# Headers_v0.net
KiCad netlist of a schematic drawn in Altium Designer
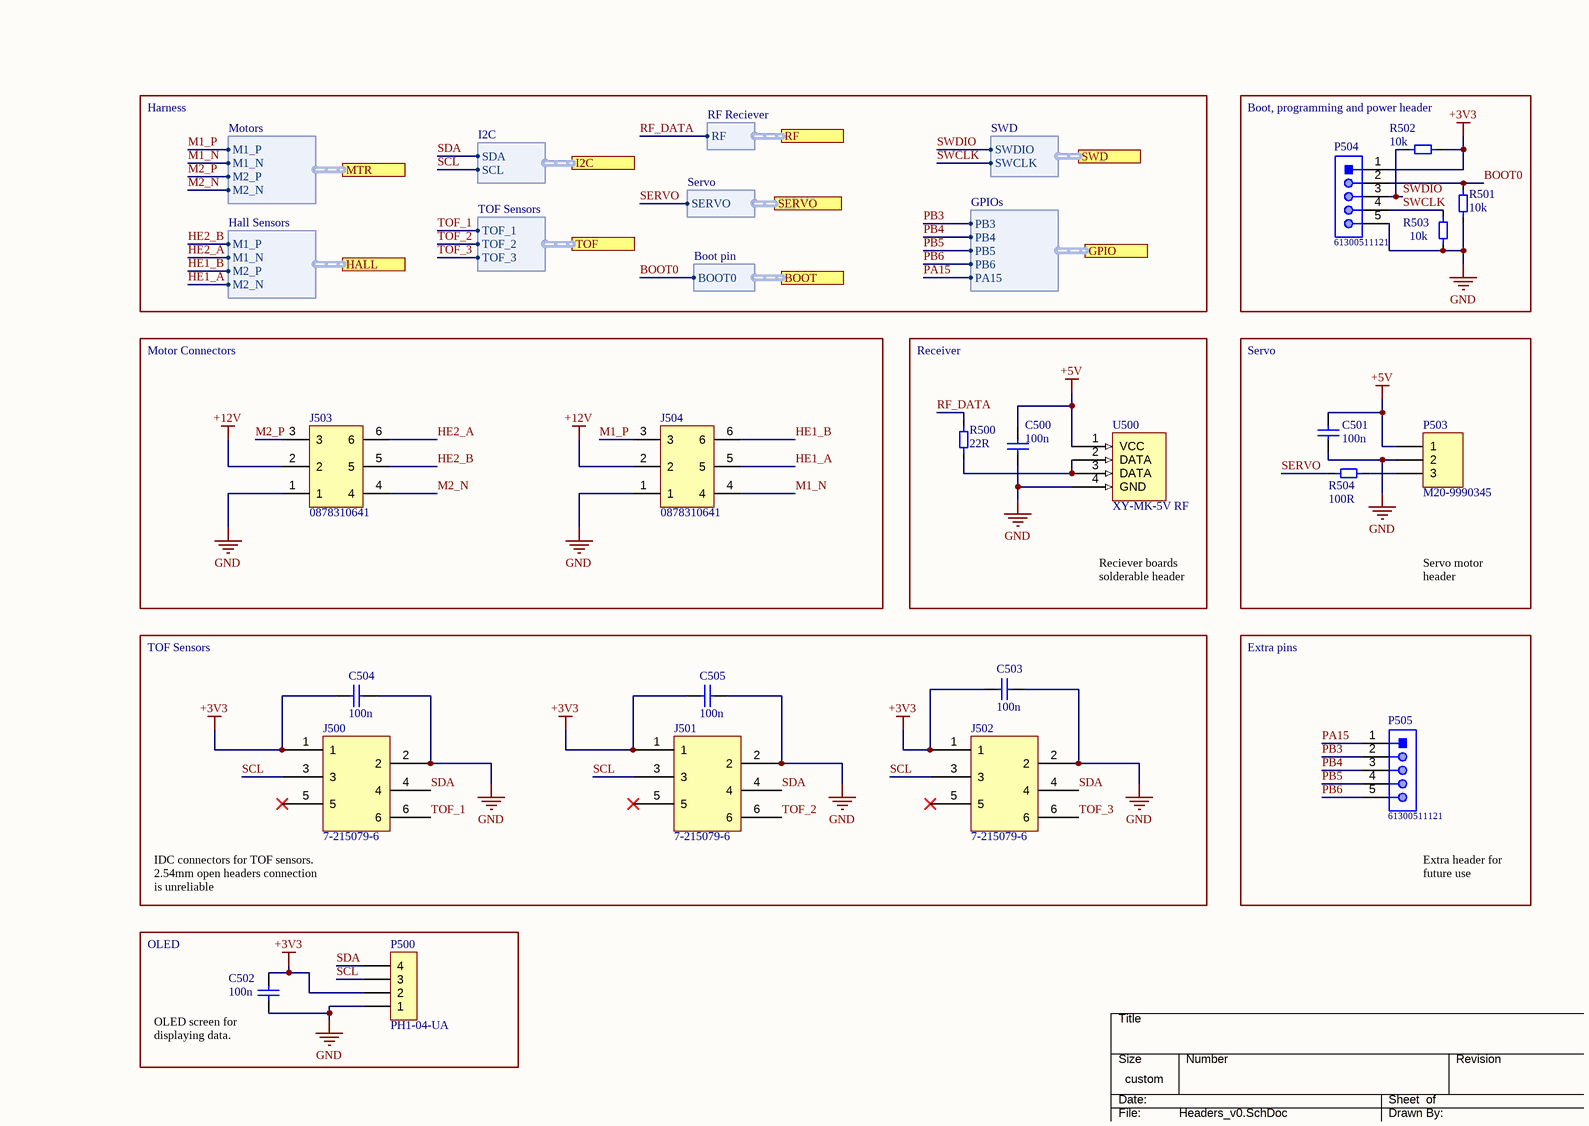
[diagram p0: Headers_v0.SchDoc]

(export (version "E")
  (design (tool "Eeschema 10.0.6"))
  (components
    (comp (ref "C500")
      (value "100n")
      (footprint "MLCC_0603_M")
      (description "MLCC, 0603, 100n, 10%, 50V, X7R")
      (fields (field (name "VOLTAGE") "50V") (field (name "TOLERANCE") "10%"))
      (libsource (lib "Krakul Vault") (part "CAPACITOR_NONPOL_IEC"))
    )
    (comp (ref "C501")
      (value "100n")
      (footprint "MLCC_0603_M")
      (description "MLCC, 0603, 100n, 10%, 50V, X7R")
      (fields (field (name "VOLTAGE") "50V") (field (name "TOLERANCE") "10%"))
      (libsource (lib "Krakul Vault") (part "CAPACITOR_NONPOL_IEC"))
    )
    (comp (ref "C502")
      (value "100n")
      (footprint "MLCC_0603_M")
      (description "MLCC, 0603, 100n, 10%, 50V, X7R")
      (fields (field (name "VOLTAGE") "50V") (field (name "TOLERANCE") "10%"))
      (libsource (lib "Krakul Vault") (part "CAPACITOR_NONPOL_IEC"))
    )
    (comp (ref "C503")
      (value "100n")
      (footprint "MLCC_0603_M")
      (description "MLCC, 0603, 100n, 10%, 50V, X7R")
      (fields (field (name "VOLTAGE") "50V") (field (name "TOLERANCE") "10%"))
      (libsource (lib "Krakul Vault") (part "CAPACITOR_NONPOL_IEC"))
    )
    (comp (ref "C504")
      (value "100n")
      (footprint "MLCC_0603_M")
      (description "MLCC, 0603, 100n, 10%, 50V, X7R")
      (fields (field (name "VOLTAGE") "50V") (field (name "TOLERANCE") "10%"))
      (libsource (lib "Krakul Vault") (part "CAPACITOR_NONPOL_IEC"))
    )
    (comp (ref "C505")
      (value "100n")
      (footprint "MLCC_0603_M")
      (description "MLCC, 0603, 100n, 10%, 50V, X7R")
      (fields (field (name "VOLTAGE") "50V") (field (name "TOLERANCE") "10%"))
      (libsource (lib "Krakul Vault") (part "CAPACITOR_NONPOL_IEC"))
    )
    (comp (ref "J500")
      (value "7-215079-6")
      (footprint "7-215079-6-Footprint-1")
      (description "Conn FFC Connector F 6 POS 1.27mm Solder ST Thru-Hole Automotive Box/Carton")
      (fields (field (name "MANUFACTURER") "TE Connectivity"))
      (libsource (lib "Krakul Vault") (part "7-215079-6"))
    )
    (comp (ref "J501")
      (value "7-215079-6")
      (footprint "7-215079-6-Footprint-1")
      (description "Conn FFC Connector F 6 POS 1.27mm Solder ST Thru-Hole Automotive Box/Carton")
      (fields (field (name "MANUFACTURER") "TE Connectivity"))
      (libsource (lib "Krakul Vault") (part "7-215079-6"))
    )
    (comp (ref "J502")
      (value "7-215079-6")
      (footprint "7-215079-6-Footprint-1")
      (description "Conn FFC Connector F 6 POS 1.27mm Solder ST Thru-Hole Automotive Box/Carton")
      (fields (field (name "MANUFACTURER") "TE Connectivity"))
      (libsource (lib "Krakul Vault") (part "7-215079-6"))
    )
    (comp (ref "J503")
      (value "0878310641")
      (footprint "0878310641")
      (description "Conn Shrouded Header (2 Sides) HDR 6 POS 2mm Solder ST Top Entry Thru-Hole Milli-Grid Tube")
      (fields (field (name "MANUFACTURER") "Molex"))
      (libsource (lib "Krakul Vault") (part "0878310641"))
    )
    (comp (ref "J504")
      (value "0878310641")
      (footprint "0878310641")
      (description "Conn Shrouded Header (2 Sides) HDR 6 POS 2mm Solder ST Top Entry Thru-Hole Milli-Grid Tube")
      (fields (field (name "MANUFACTURER") "Molex"))
      (libsource (lib "Krakul Vault") (part "0878310641"))
    )
    (comp (ref "P500")
      (value "PH1-04-UA")
      (footprint "4Pos Pin Header Vertical")
      (description "4 POS 2.54mm Vertical THT Header")
      (fields (field (name "MANUFACTURER") "Adam Tech"))
      (libsource (lib "Krakul Vault") (part "4POS GENERIC"))
    )
    (comp (ref "P503")
      (value "M20-9990345")
      (footprint "3Pos Pin Header")
      (description "Connector Header Through Hole 3 position 0.100\" (2.54mm)")
      (fields (field (name "MANUFACTURER") "Harwin Inc."))
      (libsource (lib "Krakul Vault") (part "3 pin header"))
    )
    (comp (ref "P504")
      (value "61300511121")
      (footprint "61300511121")
      (description "Conn Unshrouded Header HDR 5 POS 2.54mm Solder ST Top Entry Thru-Hole Bag")
      (fields (field (name "MANUFACTURER") "Wurth"))
      (libsource (lib "Krakul Vault") (part "WE-CN-1P-M-R5"))
    )
    (comp (ref "P505")
      (value "61300511121")
      (footprint "61300511121")
      (description "Conn Unshrouded Header HDR 5 POS 2.54mm Solder ST Top Entry Thru-Hole Bag")
      (fields (field (name "MANUFACTURER") "Wurth"))
      (libsource (lib "") (part "WE-CN-1P-M-R5_1"))
    )
    (comp (ref "R500")
      (value "22R")
      (footprint "Resistor_0603_M")
      (description "Resistor, 0603, 22R, 1%, 1/10W")
      (fields (field (name "TOLERANCE") "1%") (field (name "MANUFACTURER") "Any"))
      (libsource (lib "Krakul Vault") (part "RESISTOR_GENERIC_IEC"))
    )
    (comp (ref "R501")
      (value "10k")
      (footprint "Resistor_0603_M")
      (description "Resistor, 0603, 10k, ≤5%, ≥1/16W")
      (fields (field (name "MANUFACTURER") "Any"))
      (libsource (lib "Krakul Vault") (part "RESISTOR_GENERIC_IEC"))
    )
    (comp (ref "R502")
      (value "10k")
      (footprint "Resistor_0603_M")
      (description "Resistor, 0603, 10k, 1%, 1/10W")
      (fields (field (name "MANUFACTURER") "Any") (field (name "TOLERANCE") "1%"))
      (libsource (lib "Krakul Vault") (part "RESISTOR_GENERIC_IEC"))
    )
    (comp (ref "R503")
      (value "10k")
      (footprint "Resistor_0603_M")
      (description "Resistor, 0603, 10k, 1%, 1/10W")
      (fields (field (name "MANUFACTURER") "Any") (field (name "TOLERANCE") "1%"))
      (libsource (lib "Krakul Vault") (part "RESISTOR_GENERIC_IEC"))
    )
    (comp (ref "R504")
      (value "100R")
      (footprint "Resistor_0603_M")
      (description "Resistor, 0603, 100R, 1%, 1/10W")
      (fields (field (name "POWER") "100mW") (field (name "MANUFACTURER") "Any"))
      (libsource (lib "Krakul Vault") (part "RESISTOR_GENERIC_IEC"))
    )
    (comp (ref "U500")
      (value "XY-MK-5V RF")
      (footprint "2.54mm 4 POS XY-MK-5V RF")
      (description "433MHz reciever module, 5V tolerant")
      (fields (field (name "MANUFACTURER") "Unknown"))
      (libsource (lib "Krakul Vault") (part "XY-MK-5V RF-Symbol-1"))
    )
  )
  (nets
    (net (code "13") (name "+3V3") (class "Default")
      (node (ref "C502") (pin "1") (pinfunction "1_1") (pintype "passive"))
      (node (ref "C503") (pin "1") (pinfunction "1_1") (pintype "passive"))
      (node (ref "C504") (pin "1") (pinfunction "1_1") (pintype "passive"))
      (node (ref "C505") (pin "1") (pinfunction "1_1") (pintype "passive"))
      (node (ref "J500") (pin "1") (pinfunction "1_1") (pintype "passive"))
      (node (ref "J501") (pin "1") (pinfunction "1_1") (pintype "passive"))
      (node (ref "J502") (pin "1") (pinfunction "1_1") (pintype "passive"))
      (node (ref "P500") (pin "2") (pinfunction "2_2") (pintype "passive"))
      (node (ref "P504") (pin "1") (pinfunction "1_1") (pintype "passive"))
      (node (ref "R502") (pin "1") (pinfunction "1_1") (pintype "passive"))
    )
    (net (code "14") (name "+5V") (class "Default")
      (node (ref "C500") (pin "1") (pinfunction "1_1") (pintype "passive"))
      (node (ref "C501") (pin "1") (pinfunction "1_1") (pintype "passive"))
      (node (ref "P503") (pin "1") (pinfunction "1_1") (pintype "passive"))
      (node (ref "U500") (pin "1") (pinfunction "VCC_1") (pintype "input"))
    )
    (net (code "15") (name "+12V") (class "Default")
      (node (ref "J503") (pin "2") (pinfunction "2_2") (pintype "passive"))
      (node (ref "J504") (pin "2") (pinfunction "2_2") (pintype "passive"))
    )
    (net (code "16") (name "/BOOT0") (class "Default")
      (node (ref "P504") (pin "2") (pinfunction "2_2") (pintype "passive"))
      (node (ref "R501") (pin "2") (pinfunction "2_2") (pintype "passive"))
    )
    (net (code "17") (name "/HE1_A") (class "Default")
      (node (ref "J504") (pin "5") (pinfunction "5_5") (pintype "passive"))
    )
    (net (code "18") (name "/HE1_B") (class "Default")
      (node (ref "J504") (pin "6") (pinfunction "6_6") (pintype "passive"))
    )
    (net (code "19") (name "/HE2_A") (class "Default")
      (node (ref "J503") (pin "6") (pinfunction "6_6") (pintype "passive"))
    )
    (net (code "20") (name "/HE2_B") (class "Default")
      (node (ref "J503") (pin "5") (pinfunction "5_5") (pintype "passive"))
    )
    (net (code "21") (name "/M1_N") (class "Default")
      (node (ref "J504") (pin "4") (pinfunction "4_4") (pintype "passive"))
    )
    (net (code "22") (name "/M1_P") (class "Default")
      (node (ref "J504") (pin "3") (pinfunction "3_3") (pintype "passive"))
    )
    (net (code "23") (name "/M2_N") (class "Default")
      (node (ref "J503") (pin "4") (pinfunction "4_4") (pintype "passive"))
    )
    (net (code "24") (name "/M2_P") (class "Default")
      (node (ref "J503") (pin "3") (pinfunction "3_3") (pintype "passive"))
    )
    (net (code "25") (name "/PA15") (class "Default")
      (node (ref "P505") (pin "1") (pinfunction "1_1") (pintype "passive"))
    )
    (net (code "26") (name "/PB3") (class "Default")
      (node (ref "P505") (pin "2") (pinfunction "2_2") (pintype "passive"))
    )
    (net (code "27") (name "/PB4") (class "Default")
      (node (ref "P505") (pin "3") (pinfunction "3_3") (pintype "passive"))
    )
    (net (code "28") (name "/PB5") (class "Default")
      (node (ref "P505") (pin "4") (pinfunction "4_4") (pintype "passive"))
    )
    (net (code "29") (name "/PB6") (class "Default")
      (node (ref "P505") (pin "5") (pinfunction "5_5") (pintype "passive"))
    )
    (net (code "30") (name "/RF_DATA") (class "Default")
      (node (ref "R500") (pin "1") (pinfunction "1_1") (pintype "passive"))
    )
    (net (code "31") (name "/SCL") (class "Default")
      (node (ref "J500") (pin "3") (pinfunction "3_3") (pintype "passive"))
      (node (ref "J501") (pin "3") (pinfunction "3_3") (pintype "passive"))
      (node (ref "J502") (pin "3") (pinfunction "3_3") (pintype "passive"))
      (node (ref "P500") (pin "3") (pinfunction "3_3") (pintype "passive"))
    )
    (net (code "32") (name "/SDA") (class "Default")
      (node (ref "J500") (pin "4") (pinfunction "4_4") (pintype "passive"))
      (node (ref "J501") (pin "4") (pinfunction "4_4") (pintype "passive"))
      (node (ref "J502") (pin "4") (pinfunction "4_4") (pintype "passive"))
      (node (ref "P500") (pin "4") (pinfunction "4_4") (pintype "passive"))
    )
    (net (code "33") (name "/SERVO") (class "Default")
      (node (ref "R504") (pin "2") (pinfunction "2_2") (pintype "passive"))
    )
    (net (code "34") (name "/SWCLK") (class "Default")
      (node (ref "P504") (pin "4") (pinfunction "4_4") (pintype "passive"))
      (node (ref "R503") (pin "2") (pinfunction "2_2") (pintype "passive"))
    )
    (net (code "35") (name "/SWDIO") (class "Default")
      (node (ref "P504") (pin "3") (pinfunction "3_3") (pintype "passive"))
      (node (ref "R502") (pin "2") (pinfunction "2_2") (pintype "passive"))
    )
    (net (code "36") (name "/TOF_1") (class "Default")
      (node (ref "J500") (pin "6") (pinfunction "6_6") (pintype "passive"))
    )
    (net (code "37") (name "/TOF_2") (class "Default")
      (node (ref "J501") (pin "6") (pinfunction "6_6") (pintype "passive"))
    )
    (net (code "38") (name "/TOF_3") (class "Default")
      (node (ref "J502") (pin "6") (pinfunction "6_6") (pintype "passive"))
    )
    (net (code "48") (name "GND") (class "Default")
      (node (ref "C500") (pin "2") (pinfunction "2_2") (pintype "passive"))
      (node (ref "C501") (pin "2") (pinfunction "2_2") (pintype "passive"))
      (node (ref "C502") (pin "2") (pinfunction "2_2") (pintype "passive"))
      (node (ref "C503") (pin "2") (pinfunction "2_2") (pintype "passive"))
      (node (ref "C504") (pin "2") (pinfunction "2_2") (pintype "passive"))
      (node (ref "C505") (pin "2") (pinfunction "2_2") (pintype "passive"))
      (node (ref "J500") (pin "2") (pinfunction "2_2") (pintype "passive"))
      (node (ref "J501") (pin "2") (pinfunction "2_2") (pintype "passive"))
      (node (ref "J502") (pin "2") (pinfunction "2_2") (pintype "passive"))
      (node (ref "J503") (pin "1") (pinfunction "1_1") (pintype "passive"))
      (node (ref "J504") (pin "1") (pinfunction "1_1") (pintype "passive"))
      (node (ref "P500") (pin "1") (pinfunction "1_1") (pintype "passive"))
      (node (ref "P503") (pin "2") (pinfunction "2_2") (pintype "passive"))
      (node (ref "P504") (pin "5") (pinfunction "5_5") (pintype "passive"))
      (node (ref "R501") (pin "1") (pinfunction "1_1") (pintype "passive"))
      (node (ref "R503") (pin "1") (pinfunction "1_1") (pintype "passive"))
      (node (ref "U500") (pin "4") (pinfunction "GND_4") (pintype "input"))
    )
    (net (code "49") (name "Net-(P503-Pad3)") (class "Default")
      (node (ref "P503") (pin "3") (pinfunction "3_3") (pintype "passive"))
      (node (ref "R504") (pin "1") (pinfunction "1_1") (pintype "passive"))
    )
    (net (code "50") (name "Net-(R500-Pad2)") (class "Default")
      (node (ref "R500") (pin "2") (pinfunction "2_2") (pintype "passive"))
      (node (ref "U500") (pin "2") (pinfunction "DATA_2") (pintype "input"))
      (node (ref "U500") (pin "3") (pinfunction "DATA_3") (pintype "input"))
    )
    (net (code "51") (name "unconnected-(J500-Pad5)") (class "Default")
      (node (ref "J500") (pin "5") (pinfunction "5_5") (pintype "passive+no_connect"))
    )
    (net (code "52") (name "unconnected-(J501-Pad5)") (class "Default")
      (node (ref "J501") (pin "5") (pinfunction "5_5") (pintype "passive+no_connect"))
    )
    (net (code "53") (name "unconnected-(J502-Pad5)") (class "Default")
      (node (ref "J502") (pin "5") (pinfunction "5_5") (pintype "passive+no_connect"))
    )
  )
)
